# Calvos_Proyectointegrador.net
KiCad netlist of a schematic drawn in EAGLE
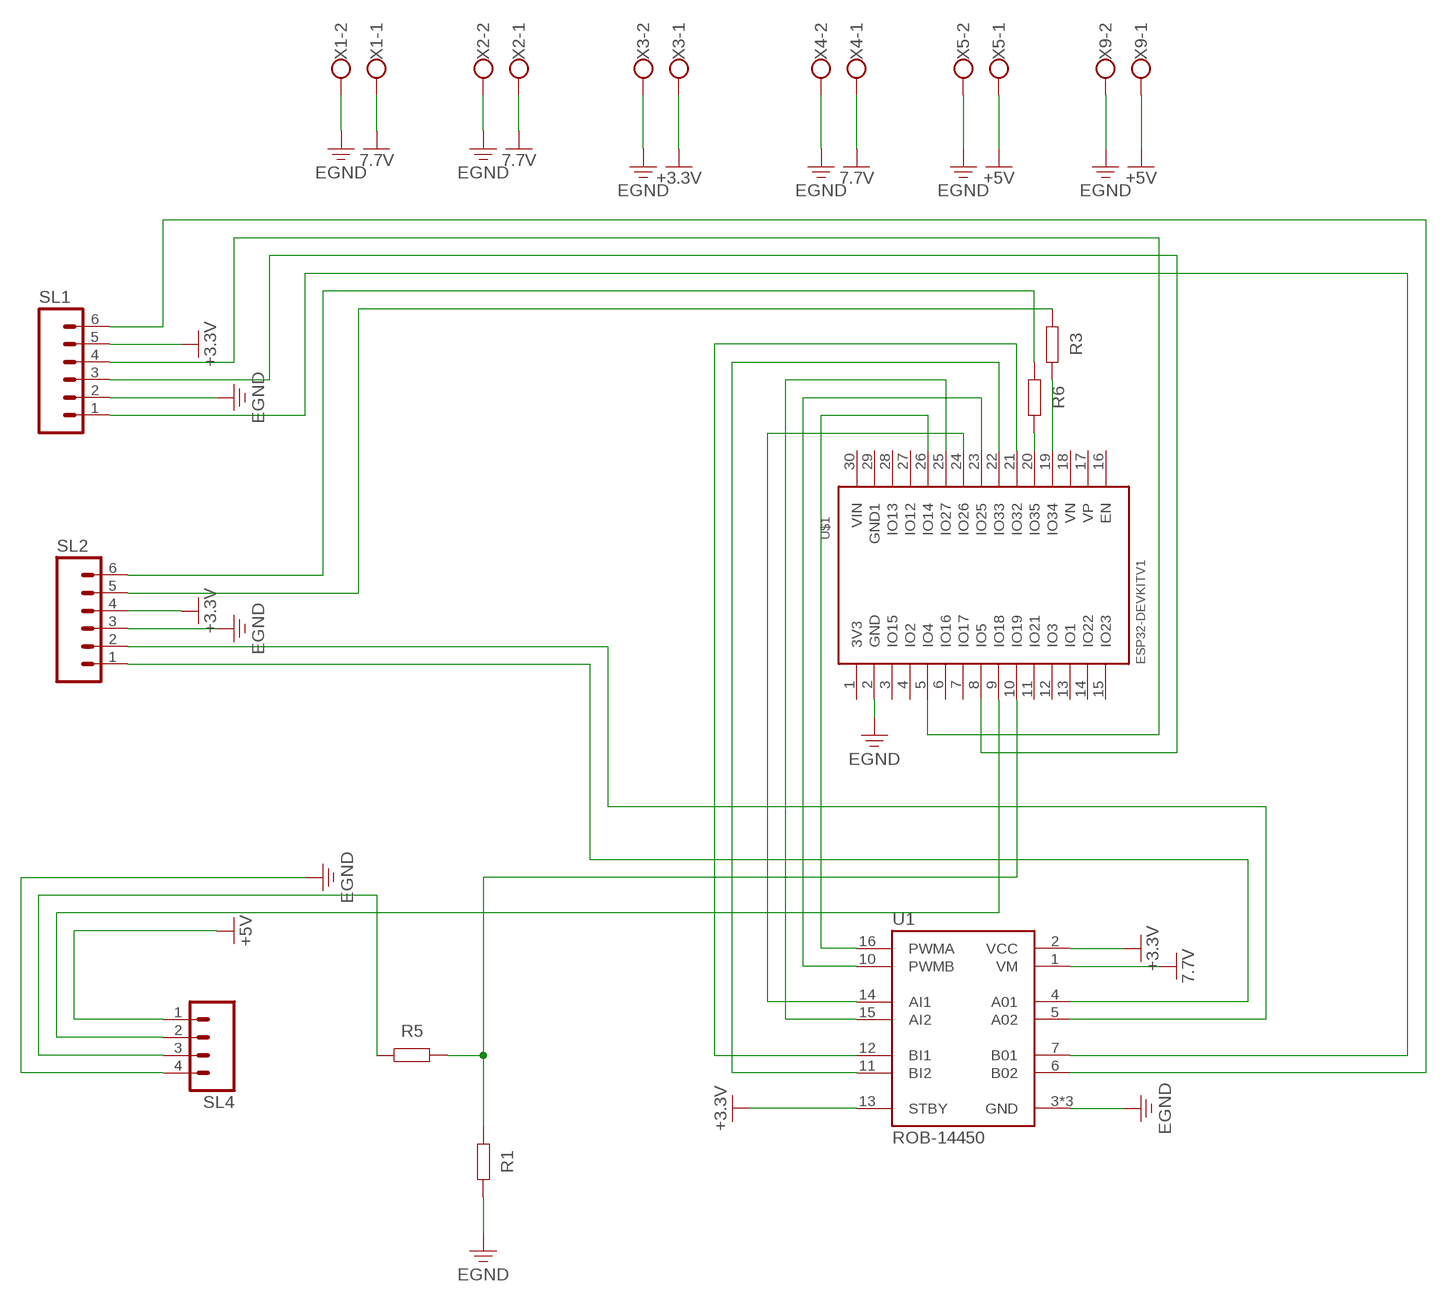
[diagram p0: schematic, sheet 1]

(export (version "E")
  (design (tool "Eeschema 10.0.6"))
  (components
    (comp (ref "R1")
      (value "R_AXIAL-7.2MM-PITCH")
      (footprint "eagle-import:RESAD724W46L381D178B")
      (libsource (lib "eagle-import") (part "RAXIAL-7.2MM-PITCH_"))
    )
    (comp (ref "R3")
      (value "R_AXIAL-7.2MM-PITCH")
      (footprint "eagle-import:RESAD724W46L381D178B")
      (libsource (lib "eagle-import") (part "RAXIAL-7.2MM-PITCH_"))
    )
    (comp (ref "R5")
      (value "R_AXIAL-7.2MM-PITCH")
      (footprint "eagle-import:RESAD724W46L381D178B")
      (libsource (lib "eagle-import") (part "RAXIAL-7.2MM-PITCH_"))
    )
    (comp (ref "R6")
      (value "R_AXIAL-7.2MM-PITCH")
      (footprint "eagle-import:RESAD724W46L381D178B")
      (libsource (lib "eagle-import") (part "RAXIAL-7.2MM-PITCH_"))
    )
    (comp (ref "SL1")
      (value "M06")
      (footprint "eagle-import:06P")
      (libsource (lib "eagle-import") (part "M06"))
    )
    (comp (ref "SL2")
      (value "M06")
      (footprint "eagle-import:06P")
      (libsource (lib "eagle-import") (part "M06"))
    )
    (comp (ref "SL4")
      (value "M04")
      (footprint "eagle-import:04P")
      (libsource (lib "eagle-import") (part "M04"))
    )
    (comp (ref "U$1")
      (value "ESP32DEVKITV1")
      (footprint "eagle-import:ESP32-DEVKITV1")
      (libsource (lib "eagle-import") (part "ESP32DEVKITV1"))
    )
    (comp (ref "U1")
      (value "ROB-14450")
      (footprint "eagle-import:MODULE_ROB-14450")
      (fields (field (name "MF") "SparkFun Electronics"))
      (libsource (lib "eagle-import") (part "ROB-14450"))
    )
    (comp (ref "X1")
      (value "W237-102")
      (footprint "eagle-import:W237-102")
      (fields (field (name "MPN") "237-102"))
      (libsource (lib "eagle-import") (part "W237-102"))
    )
    (comp (ref "X2")
      (value "W237-102")
      (footprint "eagle-import:W237-102")
      (fields (field (name "MPN") "237-102"))
      (libsource (lib "eagle-import") (part "W237-102"))
    )
    (comp (ref "X3")
      (value "W237-102")
      (footprint "eagle-import:W237-102")
      (fields (field (name "MPN") "237-102"))
      (libsource (lib "eagle-import") (part "W237-102"))
    )
    (comp (ref "X4")
      (value "W237-102")
      (footprint "eagle-import:W237-102")
      (fields (field (name "MPN") "237-102"))
      (libsource (lib "eagle-import") (part "W237-102"))
    )
    (comp (ref "X5")
      (value "W237-102")
      (footprint "eagle-import:W237-102")
      (fields (field (name "MPN") "237-102"))
      (libsource (lib "eagle-import") (part "W237-102"))
    )
    (comp (ref "X9")
      (value "W237-102")
      (footprint "eagle-import:W237-102")
      (fields (field (name "MPN") "237-102"))
      (libsource (lib "eagle-import") (part "W237-102"))
    )
  )
  (nets
    (net (code "1") (name "+3.3V") (class "Default")
      (node (ref "SL1") (pin "5") (pinfunction "5_5") (pintype "passive"))
      (node (ref "SL2") (pin "4") (pinfunction "4_4") (pintype "passive"))
      (node (ref "U1") (pin "13") (pinfunction "STBY_13") (pintype "input"))
      (node (ref "U1") (pin "2") (pinfunction "VCC_2") (pintype "power_in"))
      (node (ref "X3") (pin "1") (pinfunction "KL_1") (pintype "passive"))
    )
    (net (code "2") (name "+5V") (class "Default")
      (node (ref "SL4") (pin "1") (pinfunction "1_1") (pintype "passive"))
      (node (ref "X5") (pin "1") (pinfunction "KL_1") (pintype "passive"))
      (node (ref "X9") (pin "1") (pinfunction "KL_1") (pintype "passive"))
    )
    (net (code "3") (name "7.7V") (class "Default")
      (node (ref "U1") (pin "1") (pinfunction "VM_1") (pintype "power_in"))
      (node (ref "X1") (pin "1") (pinfunction "KL_1") (pintype "passive"))
      (node (ref "X2") (pin "1") (pinfunction "KL_1") (pintype "passive"))
      (node (ref "X4") (pin "1") (pinfunction "KL_1") (pintype "passive"))
    )
    (net (code "4") (name "EGND") (class "Default")
      (node (ref "R1") (pin "2") (pinfunction "2_2") (pintype "passive"))
      (node (ref "SL1") (pin "2") (pinfunction "2_2") (pintype "passive"))
      (node (ref "SL2") (pin "3") (pinfunction "3_3") (pintype "passive"))
      (node (ref "SL4") (pin "4") (pinfunction "4_4") (pintype "passive"))
      (node (ref "U$1") (pin "2") (pinfunction "GND_2") (pintype "bidirectional"))
      (node (ref "U1") (pin "3") (pinfunction "GND_3") (pintype "power_in"))
      (node (ref "U1") (pin "8") (pinfunction "GND_8") (pintype "power_in"))
      (node (ref "U1") (pin "9") (pinfunction "GND_9") (pintype "power_in"))
      (node (ref "X1") (pin "2") (pinfunction "KL_2") (pintype "passive"))
      (node (ref "X2") (pin "2") (pinfunction "KL_2") (pintype "passive"))
      (node (ref "X3") (pin "2") (pinfunction "KL_2") (pintype "passive"))
      (node (ref "X4") (pin "2") (pinfunction "KL_2") (pintype "passive"))
      (node (ref "X5") (pin "2") (pinfunction "KL_2") (pintype "passive"))
      (node (ref "X9") (pin "2") (pinfunction "KL_2") (pintype "passive"))
    )
    (net (code "5") (name "Net-(R3-Pad1)") (class "Default")
      (node (ref "R3") (pin "1") (pinfunction "1_1") (pintype "passive"))
      (node (ref "SL2") (pin "5") (pinfunction "5_5") (pintype "passive"))
    )
    (net (code "6") (name "Net-(R5-Pad1)") (class "Default")
      (node (ref "R5") (pin "1") (pinfunction "1_1") (pintype "passive"))
      (node (ref "SL4") (pin "3") (pinfunction "3_3") (pintype "passive"))
    )
    (net (code "7") (name "Net-(R6-Pad1)") (class "Default")
      (node (ref "R6") (pin "1") (pinfunction "1_1") (pintype "passive"))
      (node (ref "SL2") (pin "6") (pinfunction "6_6") (pintype "passive"))
    )
    (net (code "8") (name "Net-(U$1-IO4)") (class "Default")
      (node (ref "SL1") (pin "4") (pinfunction "4_4") (pintype "passive"))
      (node (ref "U$1") (pin "5") (pinfunction "IO4_5") (pintype "bidirectional"))
    )
    (net (code "9") (name "Net-(U$1-IO5)") (class "Default")
      (node (ref "SL1") (pin "3") (pinfunction "3_3") (pintype "passive"))
      (node (ref "U$1") (pin "8") (pinfunction "IO5_8") (pintype "bidirectional"))
    )
    (net (code "10") (name "Net-(U$1-IO14)") (class "Default")
      (node (ref "U$1") (pin "26") (pinfunction "IO14_26") (pintype "bidirectional"))
      (node (ref "U1") (pin "16") (pinfunction "PWMA_16") (pintype "input"))
    )
    (net (code "11") (name "Net-(U$1-IO18)") (class "Default")
      (node (ref "SL4") (pin "2") (pinfunction "2_2") (pintype "passive"))
      (node (ref "U$1") (pin "9") (pinfunction "IO18_9") (pintype "bidirectional"))
    )
    (net (code "12") (name "Net-(U$1-IO19)") (class "Default")
      (node (ref "R1") (pin "1") (pinfunction "1_1") (pintype "passive"))
      (node (ref "R5") (pin "2") (pinfunction "2_2") (pintype "passive"))
      (node (ref "U$1") (pin "10") (pinfunction "IO19_10") (pintype "bidirectional"))
    )
    (net (code "13") (name "Net-(U$1-IO25)") (class "Default")
      (node (ref "U$1") (pin "23") (pinfunction "IO25_23") (pintype "bidirectional"))
      (node (ref "U1") (pin "10") (pinfunction "PWMB_10") (pintype "input"))
    )
    (net (code "14") (name "Net-(U$1-IO26)") (class "Default")
      (node (ref "U$1") (pin "24") (pinfunction "IO26_24") (pintype "bidirectional"))
      (node (ref "U1") (pin "14") (pinfunction "AI1_14") (pintype "input"))
    )
    (net (code "15") (name "Net-(U$1-IO27)") (class "Default")
      (node (ref "U$1") (pin "25") (pinfunction "IO27_25") (pintype "bidirectional"))
      (node (ref "U1") (pin "15") (pinfunction "AI2_15") (pintype "input"))
    )
    (net (code "16") (name "Net-(U$1-IO32)") (class "Default")
      (node (ref "U$1") (pin "21") (pinfunction "IO32_21") (pintype "bidirectional"))
      (node (ref "U1") (pin "12") (pinfunction "BI1_12") (pintype "input"))
    )
    (net (code "17") (name "Net-(U$1-IO33)") (class "Default")
      (node (ref "U$1") (pin "22") (pinfunction "IO33_22") (pintype "bidirectional"))
      (node (ref "U1") (pin "11") (pinfunction "BI2_11") (pintype "input"))
    )
    (net (code "18") (name "Net-(U$1-IO34)") (class "Default")
      (node (ref "R3") (pin "2") (pinfunction "2_2") (pintype "passive"))
      (node (ref "U$1") (pin "19") (pinfunction "IO34_19") (pintype "bidirectional"))
    )
    (net (code "19") (name "Net-(U$1-IO35)") (class "Default")
      (node (ref "R6") (pin "2") (pinfunction "2_2") (pintype "passive"))
      (node (ref "U$1") (pin "20") (pinfunction "IO35_20") (pintype "bidirectional"))
    )
    (net (code "20") (name "Net-(U1-A01)") (class "Default")
      (node (ref "SL2") (pin "1") (pinfunction "1_1") (pintype "passive"))
      (node (ref "U1") (pin "4") (pinfunction "A01_4") (pintype "output"))
    )
    (net (code "21") (name "Net-(U1-A02)") (class "Default")
      (node (ref "SL2") (pin "2") (pinfunction "2_2") (pintype "passive"))
      (node (ref "U1") (pin "5") (pinfunction "A02_5") (pintype "output"))
    )
    (net (code "22") (name "Net-(U1-B01)") (class "Default")
      (node (ref "SL1") (pin "1") (pinfunction "1_1") (pintype "passive"))
      (node (ref "U1") (pin "7") (pinfunction "B01_7") (pintype "output"))
    )
    (net (code "23") (name "Net-(U1-B02)") (class "Default")
      (node (ref "SL1") (pin "6") (pinfunction "6_6") (pintype "passive"))
      (node (ref "U1") (pin "6") (pinfunction "B02_6") (pintype "output"))
    )
    (net (code "24") (name "unconnected-(U$1-3V3-Pad1)") (class "Default")
      (node (ref "U$1") (pin "1") (pinfunction "3V3_1") (pintype "bidirectional"))
    )
    (net (code "25") (name "unconnected-(U$1-EN-Pad16)") (class "Default")
      (node (ref "U$1") (pin "16") (pinfunction "EN_16") (pintype "bidirectional"))
    )
    (net (code "26") (name "unconnected-(U$1-GND1-Pad29)") (class "Default")
      (node (ref "U$1") (pin "29") (pinfunction "GND1_29") (pintype "bidirectional"))
    )
    (net (code "27") (name "unconnected-(U$1-IO1-Pad13)") (class "Default")
      (node (ref "U$1") (pin "13") (pinfunction "IO1_13") (pintype "bidirectional"))
    )
    (net (code "28") (name "unconnected-(U$1-IO2-Pad4)") (class "Default")
      (node (ref "U$1") (pin "4") (pinfunction "IO2_4") (pintype "bidirectional"))
    )
    (net (code "29") (name "unconnected-(U$1-IO3-Pad12)") (class "Default")
      (node (ref "U$1") (pin "12") (pinfunction "IO3_12") (pintype "bidirectional"))
    )
    (net (code "30") (name "unconnected-(U$1-IO12-Pad27)") (class "Default")
      (node (ref "U$1") (pin "27") (pinfunction "IO12_27") (pintype "bidirectional"))
    )
    (net (code "31") (name "unconnected-(U$1-IO13-Pad28)") (class "Default")
      (node (ref "U$1") (pin "28") (pinfunction "IO13_28") (pintype "bidirectional"))
    )
    (net (code "32") (name "unconnected-(U$1-IO15-Pad3)") (class "Default")
      (node (ref "U$1") (pin "3") (pinfunction "IO15_3") (pintype "bidirectional"))
    )
    (net (code "33") (name "unconnected-(U$1-IO16-Pad6)") (class "Default")
      (node (ref "U$1") (pin "6") (pinfunction "IO16_6") (pintype "bidirectional"))
    )
    (net (code "34") (name "unconnected-(U$1-IO17-Pad7)") (class "Default")
      (node (ref "U$1") (pin "7") (pinfunction "IO17_7") (pintype "bidirectional"))
    )
    (net (code "35") (name "unconnected-(U$1-IO21-Pad11)") (class "Default")
      (node (ref "U$1") (pin "11") (pinfunction "IO21_11") (pintype "bidirectional"))
    )
    (net (code "36") (name "unconnected-(U$1-IO22-Pad14)") (class "Default")
      (node (ref "U$1") (pin "14") (pinfunction "IO22_14") (pintype "bidirectional"))
    )
    (net (code "37") (name "unconnected-(U$1-IO23-Pad15)") (class "Default")
      (node (ref "U$1") (pin "15") (pinfunction "IO23_15") (pintype "bidirectional"))
    )
    (net (code "38") (name "unconnected-(U$1-VIN-Pad30)") (class "Default")
      (node (ref "U$1") (pin "30") (pinfunction "VIN_30") (pintype "bidirectional"))
    )
    (net (code "39") (name "unconnected-(U$1-VN-Pad18)") (class "Default")
      (node (ref "U$1") (pin "18") (pinfunction "VN_18") (pintype "bidirectional"))
    )
    (net (code "40") (name "unconnected-(U$1-VP-Pad17)") (class "Default")
      (node (ref "U$1") (pin "17") (pinfunction "VP_17") (pintype "bidirectional"))
    )
  )
)
